# RTC.net
KiCad netlist of a schematic drawn in EAGLE
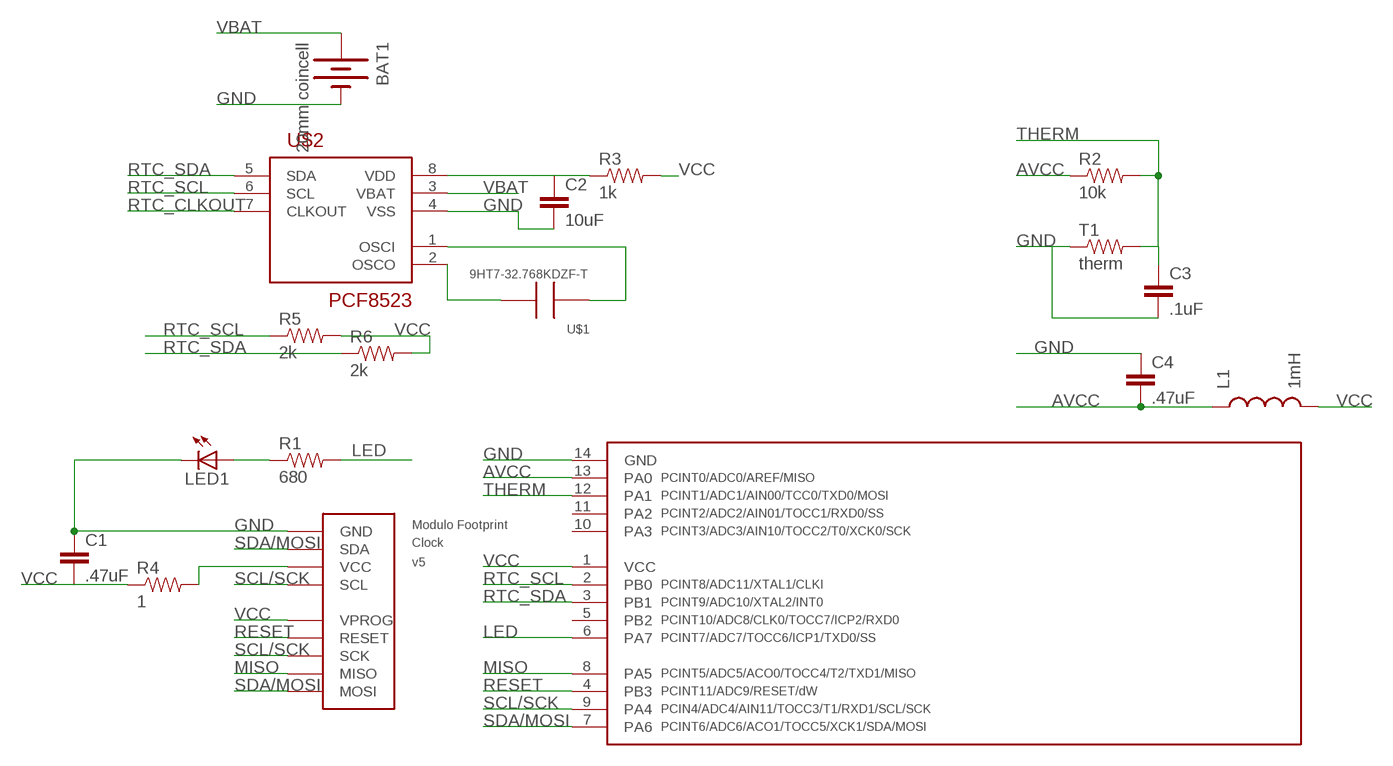
[diagram p0: schematic, sheet 1]

(export (version "E")
  (design (tool "Eeschema 10.0.6"))
  (components
    (comp (ref "BAT1")
      (value "20mm coincell")
      (footprint "eagle-import:BATTCON_20MM_4LEGS")
      (libsource (lib "eagle-import") (part "BATTERY20MM_4LEGS"))
    )
    (comp (ref "C1")
      (value ".47uF")
      (footprint "eagle-import:0805")
      (libsource (lib "eagle-import") (part "CAP0805"))
    )
    (comp (ref "C2")
      (value "10uF")
      (footprint "eagle-import:0805")
      (libsource (lib "eagle-import") (part "SparkFun-Passives_CAP0805"))
    )
    (comp (ref "C3")
      (value ".1uF")
      (footprint "eagle-import:0805")
      (libsource (lib "eagle-import") (part "CAP0805"))
    )
    (comp (ref "C4")
      (value ".47uF")
      (footprint "eagle-import:0805")
      (libsource (lib "eagle-import") (part "CAP0805"))
    )
    (comp (ref "L1")
      (value "1mH")
      (footprint "eagle-import:1007")
      (libsource (lib "eagle-import") (part "INDUCTOR1007"))
    )
    (comp (ref "LED1")
      (value "LEDCHIP-LED0805")
      (footprint "eagle-import:CHIP-LED0805")
      (libsource (lib "eagle-import") (part "LEDCHIP-LED0805"))
    )
    (comp (ref "R1")
      (value "680")
      (footprint "eagle-import:0805")
      (libsource (lib "eagle-import") (part "RESISTOR0805-RES"))
    )
    (comp (ref "R2")
      (value "10k")
      (footprint "eagle-import:0805")
      (libsource (lib "eagle-import") (part "RESISTOR0805-RES"))
    )
    (comp (ref "R3")
      (value "1k")
      (footprint "eagle-import:0805")
      (libsource (lib "eagle-import") (part "RESISTOR0805-RES"))
    )
    (comp (ref "R4")
      (value "1")
      (footprint "eagle-import:0805")
      (libsource (lib "eagle-import") (part "SparkFun-Resistors_RESISTOR0805-RES"))
    )
    (comp (ref "R5")
      (value "2k")
      (footprint "eagle-import:0805")
      (libsource (lib "eagle-import") (part "SparkFun-Resistors_RESISTOR0805-RES"))
    )
    (comp (ref "R6")
      (value "2k")
      (footprint "eagle-import:0805")
      (libsource (lib "eagle-import") (part "SparkFun-Resistors_RESISTOR0805-RES"))
    )
    (comp (ref "T1")
      (value "therm")
      (footprint "eagle-import:0805")
      (libsource (lib "eagle-import") (part "RESISTOR0805-RES"))
    )
    (comp (ref "U$1")
      (value "9HT7-32.768KDZF-T")
      (footprint "eagle-import:CRYSTAL-ABS25")
      (libsource (lib "eagle-import") (part "CRYSTALABS25"))
    )
    (comp (ref "U$2")
      (value "PCF8523")
      (footprint "eagle-import:SOIC-8")
      (libsource (lib "eagle-import") (part "PCF8523"))
    )
    (comp (ref "U$3")
      (value "TINY841")
      (footprint "eagle-import:SOIC14")
      (libsource (lib "eagle-import") (part "TINY841"))
    )
    (comp (ref "U$4")
      (value "FOOTPRINTFOOTPRINT-2")
      (footprint "eagle-import:FOOTPRINT2")
      (fields (field (name "BOARD") "Clock") (field (name "VERSION") "v5"))
      (libsource (lib "eagle-import") (part "FOOTPRINTFOOTPRINT-2"))
    )
  )
  (nets
    (net (code "1") (name "/AVCC") (class "Default")
      (node (ref "C4") (pin "2") (pinfunction "2_2") (pintype "passive"))
      (node (ref "L1") (pin "1") (pinfunction "1_1") (pintype "passive"))
      (node (ref "R2") (pin "1") (pinfunction "1_1") (pintype "passive"))
      (node (ref "U$3") (pin "13") (pinfunction "PA0_13") (pintype "bidirectional"))
    )
    (net (code "2") (name "/GND") (class "Default")
      (node (ref "BAT1") (pin "2") (pinfunction "-_2") (pintype "power_in"))
      (node (ref "C1") (pin "1") (pinfunction "1_1") (pintype "passive"))
      (node (ref "C2") (pin "2") (pinfunction "2_2") (pintype "passive"))
      (node (ref "C3") (pin "2") (pinfunction "2_2") (pintype "passive"))
      (node (ref "C4") (pin "1") (pinfunction "1_1") (pintype "passive"))
      (node (ref "LED1") (pin "C") (pinfunction "C_C") (pintype "passive"))
      (node (ref "T1") (pin "1") (pinfunction "1_1") (pintype "passive"))
      (node (ref "U$2") (pin "4") (pinfunction "VSS_4") (pintype "bidirectional"))
      (node (ref "U$3") (pin "14") (pinfunction "GND_14") (pintype "bidirectional"))
      (node (ref "U$4") (pin "BUS0") (pinfunction "GND_BUS0") (pintype "bidirectional"))
    )
    (net (code "3") (name "/LED") (class "Default")
      (node (ref "R1") (pin "2") (pinfunction "2_2") (pintype "passive"))
      (node (ref "U$3") (pin "6") (pinfunction "PA7_6") (pintype "bidirectional"))
    )
    (net (code "4") (name "/MISO") (class "Default")
      (node (ref "U$3") (pin "8") (pinfunction "PA5_8") (pintype "bidirectional"))
      (node (ref "U$4") (pin "PROG3") (pinfunction "MISO_PROG3") (pintype "bidirectional"))
    )
    (net (code "5") (name "/RESET") (class "Default")
      (node (ref "U$3") (pin "4") (pinfunction "PB3_4") (pintype "bidirectional"))
      (node (ref "U$4") (pin "PROG1") (pinfunction "RESET_PROG1") (pintype "bidirectional"))
    )
    (net (code "6") (name "/RTC_CLKOUT") (class "Default")
      (node (ref "U$2") (pin "7") (pinfunction "CLKOUT_7") (pintype "bidirectional"))
    )
    (net (code "7") (name "/RTC_SCL") (class "Default")
      (node (ref "R5") (pin "1") (pinfunction "1_1") (pintype "passive"))
      (node (ref "U$2") (pin "6") (pinfunction "SCL_6") (pintype "bidirectional"))
      (node (ref "U$3") (pin "2") (pinfunction "PB0_2") (pintype "bidirectional"))
    )
    (net (code "8") (name "/RTC_SDA") (class "Default")
      (node (ref "R6") (pin "1") (pinfunction "1_1") (pintype "passive"))
      (node (ref "U$2") (pin "5") (pinfunction "SDA_5") (pintype "bidirectional"))
      (node (ref "U$3") (pin "3") (pinfunction "PB1_3") (pintype "bidirectional"))
    )
    (net (code "9") (name "/SCL{slash}SCK") (class "Default")
      (node (ref "U$3") (pin "9") (pinfunction "PA4_9") (pintype "bidirectional"))
      (node (ref "U$4") (pin "BUS3") (pinfunction "SCL_BUS3") (pintype "bidirectional"))
      (node (ref "U$4") (pin "PROG2") (pinfunction "SCK_PROG2") (pintype "bidirectional"))
    )
    (net (code "10") (name "/SDA{slash}MOSI") (class "Default")
      (node (ref "U$3") (pin "7") (pinfunction "PA6_7") (pintype "bidirectional"))
      (node (ref "U$4") (pin "BUS1") (pinfunction "SDA_BUS1") (pintype "bidirectional"))
      (node (ref "U$4") (pin "PROG4") (pinfunction "MOSI_PROG4") (pintype "bidirectional"))
    )
    (net (code "11") (name "/THERM") (class "Default")
      (node (ref "C3") (pin "1") (pinfunction "1_1") (pintype "passive"))
      (node (ref "R2") (pin "2") (pinfunction "2_2") (pintype "passive"))
      (node (ref "T1") (pin "2") (pinfunction "2_2") (pintype "passive"))
      (node (ref "U$3") (pin "12") (pinfunction "PA1_12") (pintype "bidirectional"))
    )
    (net (code "12") (name "/VBAT") (class "Default")
      (node (ref "BAT1") (pin "1") (pinfunction "+_1") (pintype "power_in"))
      (node (ref "U$2") (pin "3") (pinfunction "VBAT_3") (pintype "bidirectional"))
    )
    (net (code "13") (name "/VCC") (class "Default")
      (node (ref "C1") (pin "2") (pinfunction "2_2") (pintype "passive"))
      (node (ref "L1") (pin "2") (pinfunction "2_2") (pintype "passive"))
      (node (ref "R3") (pin "2") (pinfunction "2_2") (pintype "passive"))
      (node (ref "R4") (pin "1") (pinfunction "1_1") (pintype "passive"))
      (node (ref "R5") (pin "2") (pinfunction "2_2") (pintype "passive"))
      (node (ref "R6") (pin "2") (pinfunction "2_2") (pintype "passive"))
      (node (ref "U$3") (pin "1") (pinfunction "VCC_1") (pintype "bidirectional"))
      (node (ref "U$4") (pin "PROG0") (pinfunction "VPROG_PROG0") (pintype "bidirectional"))
    )
    (net (code "14") (name "Net-(LED1-PadA)") (class "Default")
      (node (ref "LED1") (pin "A") (pinfunction "A_A") (pintype "passive"))
      (node (ref "R1") (pin "1") (pinfunction "1_1") (pintype "passive"))
    )
    (net (code "15") (name "Net-(U$1-P$2)") (class "Default")
      (node (ref "U$1") (pin "P$4") (pinfunction "P$2_P$4") (pintype "bidirectional"))
      (node (ref "U$2") (pin "2") (pinfunction "OSCO_2") (pintype "bidirectional"))
    )
    (net (code "16") (name "Net-(U$2-OSCI)") (class "Default")
      (node (ref "U$1") (pin "P$1") (pinfunction "P$1_P$1") (pintype "bidirectional"))
      (node (ref "U$2") (pin "1") (pinfunction "OSCI_1") (pintype "bidirectional"))
    )
    (net (code "17") (name "Net-(U$2-VDD)") (class "Default")
      (node (ref "C2") (pin "1") (pinfunction "1_1") (pintype "passive"))
      (node (ref "R3") (pin "1") (pinfunction "1_1") (pintype "passive"))
      (node (ref "U$2") (pin "8") (pinfunction "VDD_8") (pintype "bidirectional"))
    )
    (net (code "18") (name "Net-(U$4-VCC)") (class "Default")
      (node (ref "R4") (pin "2") (pinfunction "2_2") (pintype "passive"))
      (node (ref "U$4") (pin "BUS2") (pinfunction "VCC_BUS2") (pintype "bidirectional"))
    )
    (net (code "19") (name "unconnected-(U$3-PA2-Pad11)") (class "Default")
      (node (ref "U$3") (pin "11") (pinfunction "PA2_11") (pintype "bidirectional"))
    )
    (net (code "20") (name "unconnected-(U$3-PA3-Pad10)") (class "Default")
      (node (ref "U$3") (pin "10") (pinfunction "PA3_10") (pintype "bidirectional"))
    )
    (net (code "21") (name "unconnected-(U$3-PB2-Pad5)") (class "Default")
      (node (ref "U$3") (pin "5") (pinfunction "PB2_5") (pintype "bidirectional"))
    )
  )
)
